# H-API_AMP.net
KiCad netlist of a schematic drawn in EAGLE
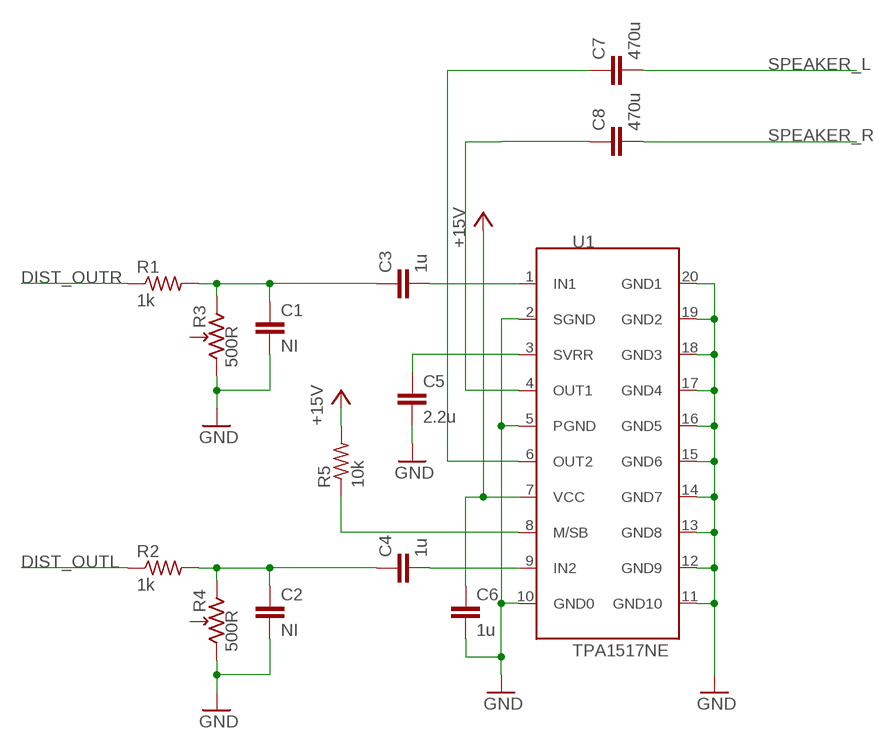
[diagram p0: schematic, sheet 1]

(export (version "E")
  (design (tool "Eeschema 10.0.6"))
  (components
    (comp (ref "C1")
      (value "NI")
      (footprint "eagle-import:C0805")
      (libsource (lib "eagle-import") (part "resistor_348_C-EUC0805"))
    )
    (comp (ref "C2")
      (value "NI")
      (footprint "eagle-import:C0805")
      (libsource (lib "eagle-import") (part "resistor_348_C-EUC0805"))
    )
    (comp (ref "C3")
      (value "1u")
      (footprint "eagle-import:C0805")
      (libsource (lib "eagle-import") (part "C-EUC0805"))
    )
    (comp (ref "C4")
      (value "1u")
      (footprint "eagle-import:C0805")
      (libsource (lib "eagle-import") (part "C-EUC0805"))
    )
    (comp (ref "C5")
      (value "2.2u")
      (footprint "eagle-import:C0805")
      (libsource (lib "eagle-import") (part "C-EUC0805"))
    )
    (comp (ref "C6")
      (value "1u")
      (footprint "eagle-import:C0805")
      (libsource (lib "eagle-import") (part "C-EUC0805"))
    )
    (comp (ref "C7")
      (value "470u")
      (footprint "eagle-import:C0805")
      (libsource (lib "eagle-import") (part "C-EUC0805"))
    )
    (comp (ref "C8")
      (value "470u")
      (footprint "eagle-import:C0805")
      (libsource (lib "eagle-import") (part "C-EUC0805"))
    )
    (comp (ref "R1")
      (value "1k")
      (footprint "eagle-import:VMTA55")
      (libsource (lib "eagle-import") (part "R-US_VMTA55"))
    )
    (comp (ref "R2")
      (value "1k")
      (footprint "eagle-import:VMTA55")
      (libsource (lib "eagle-import") (part "R-US_VMTA55"))
    )
    (comp (ref "R3")
      (value "500R")
      (footprint "eagle-import:CT6")
      (libsource (lib "eagle-import") (part "TRIM-POT"))
    )
    (comp (ref "R4")
      (value "500R")
      (footprint "eagle-import:CT6")
      (libsource (lib "eagle-import") (part "TRIM-POT"))
    )
    (comp (ref "R5")
      (value "10k")
      (footprint "eagle-import:VTA55")
      (libsource (lib "eagle-import") (part "R-US_VTA55"))
    )
    (comp (ref "U1")
      (value "TPA1517NE")
      (footprint "eagle-import:DIP20")
      (libsource (lib "eagle-import") (part "TPA1517NE"))
    )
  )
  (nets
    (net (code "1") (name "+15V") (class "Default")
      (node (ref "C6") (pin "1") (pinfunction "1_1") (pintype "passive"))
      (node (ref "R5") (pin "2") (pinfunction "2_2") (pintype "passive"))
      (node (ref "U1") (pin "7") (pinfunction "VCC_7") (pintype "input"))
    )
    (net (code "2") (name "/DIST_OUTL") (class "Default")
      (node (ref "R2") (pin "1") (pinfunction "1_1") (pintype "passive"))
    )
    (net (code "3") (name "/DIST_OUTR") (class "Default")
      (node (ref "R1") (pin "1") (pinfunction "1_1") (pintype "passive"))
    )
    (net (code "4") (name "/SPEAKER_L") (class "Default")
      (node (ref "C7") (pin "2") (pinfunction "2_2") (pintype "passive"))
    )
    (net (code "5") (name "/SPEAKER_R") (class "Default")
      (node (ref "C8") (pin "2") (pinfunction "2_2") (pintype "passive"))
    )
    (net (code "6") (name "GND") (class "Default")
      (node (ref "C1") (pin "2") (pinfunction "2_2") (pintype "passive"))
      (node (ref "C2") (pin "2") (pinfunction "2_2") (pintype "passive"))
      (node (ref "C5") (pin "2") (pinfunction "2_2") (pintype "passive"))
      (node (ref "C6") (pin "2") (pinfunction "2_2") (pintype "passive"))
      (node (ref "R3") (pin "A") (pinfunction "1_A") (pintype "bidirectional"))
      (node (ref "R4") (pin "A") (pinfunction "1_A") (pintype "bidirectional"))
      (node (ref "U1") (pin "10") (pinfunction "GND0_10") (pintype "bidirectional"))
      (node (ref "U1") (pin "11") (pinfunction "GND10_11") (pintype "bidirectional"))
      (node (ref "U1") (pin "12") (pinfunction "GND9_12") (pintype "bidirectional"))
      (node (ref "U1") (pin "13") (pinfunction "GND8_13") (pintype "bidirectional"))
      (node (ref "U1") (pin "14") (pinfunction "GND7_14") (pintype "bidirectional"))
      (node (ref "U1") (pin "15") (pinfunction "GND6_15") (pintype "bidirectional"))
      (node (ref "U1") (pin "16") (pinfunction "GND5_16") (pintype "bidirectional"))
      (node (ref "U1") (pin "17") (pinfunction "GND4_17") (pintype "bidirectional"))
      (node (ref "U1") (pin "18") (pinfunction "GND3_18") (pintype "bidirectional"))
      (node (ref "U1") (pin "19") (pinfunction "GND2_19") (pintype "bidirectional"))
      (node (ref "U1") (pin "2") (pinfunction "SGND_2") (pintype "bidirectional"))
      (node (ref "U1") (pin "20") (pinfunction "GND1_20") (pintype "bidirectional"))
      (node (ref "U1") (pin "5") (pinfunction "PGND_5") (pintype "bidirectional"))
    )
    (net (code "7") (name "Net-(R3-3)") (class "Default")
      (node (ref "C1") (pin "1") (pinfunction "1_1") (pintype "passive"))
      (node (ref "C3") (pin "1") (pinfunction "1_1") (pintype "passive"))
      (node (ref "R1") (pin "2") (pinfunction "2_2") (pintype "passive"))
      (node (ref "R3") (pin "E") (pinfunction "3_E") (pintype "bidirectional"))
    )
    (net (code "8") (name "Net-(R4-3)") (class "Default")
      (node (ref "C2") (pin "1") (pinfunction "1_1") (pintype "passive"))
      (node (ref "C4") (pin "1") (pinfunction "1_1") (pintype "passive"))
      (node (ref "R2") (pin "2") (pinfunction "2_2") (pintype "passive"))
      (node (ref "R4") (pin "E") (pinfunction "3_E") (pintype "bidirectional"))
    )
    (net (code "9") (name "Net-(U1-IN1)") (class "Default")
      (node (ref "C3") (pin "2") (pinfunction "2_2") (pintype "passive"))
      (node (ref "U1") (pin "1") (pinfunction "IN1_1") (pintype "input"))
    )
    (net (code "10") (name "Net-(U1-IN2)") (class "Default")
      (node (ref "C4") (pin "2") (pinfunction "2_2") (pintype "passive"))
      (node (ref "U1") (pin "9") (pinfunction "IN2_9") (pintype "input"))
    )
    (net (code "11") (name "Net-(U1-M{slash}SB)") (class "Default")
      (node (ref "R5") (pin "1") (pinfunction "1_1") (pintype "passive"))
      (node (ref "U1") (pin "8") (pinfunction "M/SB_8") (pintype "input"))
    )
    (net (code "12") (name "Net-(U1-OUT1)") (class "Default")
      (node (ref "C8") (pin "1") (pinfunction "1_1") (pintype "passive"))
      (node (ref "U1") (pin "4") (pinfunction "OUT1_4") (pintype "output"))
    )
    (net (code "13") (name "Net-(U1-OUT2)") (class "Default")
      (node (ref "C7") (pin "1") (pinfunction "1_1") (pintype "passive"))
      (node (ref "U1") (pin "6") (pinfunction "OUT2_6") (pintype "output"))
    )
    (net (code "14") (name "Net-(U1-SVRR)") (class "Default")
      (node (ref "C5") (pin "1") (pinfunction "1_1") (pintype "passive"))
      (node (ref "U1") (pin "3") (pinfunction "SVRR_3") (pintype "bidirectional"))
    )
    (net (code "15") (name "unconnected-(R3-2-PadS)") (class "Default")
      (node (ref "R3") (pin "S") (pinfunction "2_S") (pintype "bidirectional"))
    )
    (net (code "16") (name "unconnected-(R4-2-PadS)") (class "Default")
      (node (ref "R4") (pin "S") (pinfunction "2_S") (pintype "bidirectional"))
    )
  )
)
